# Buck_Boost_Converter.net
KiCad netlist of a schematic drawn in Altium Designer
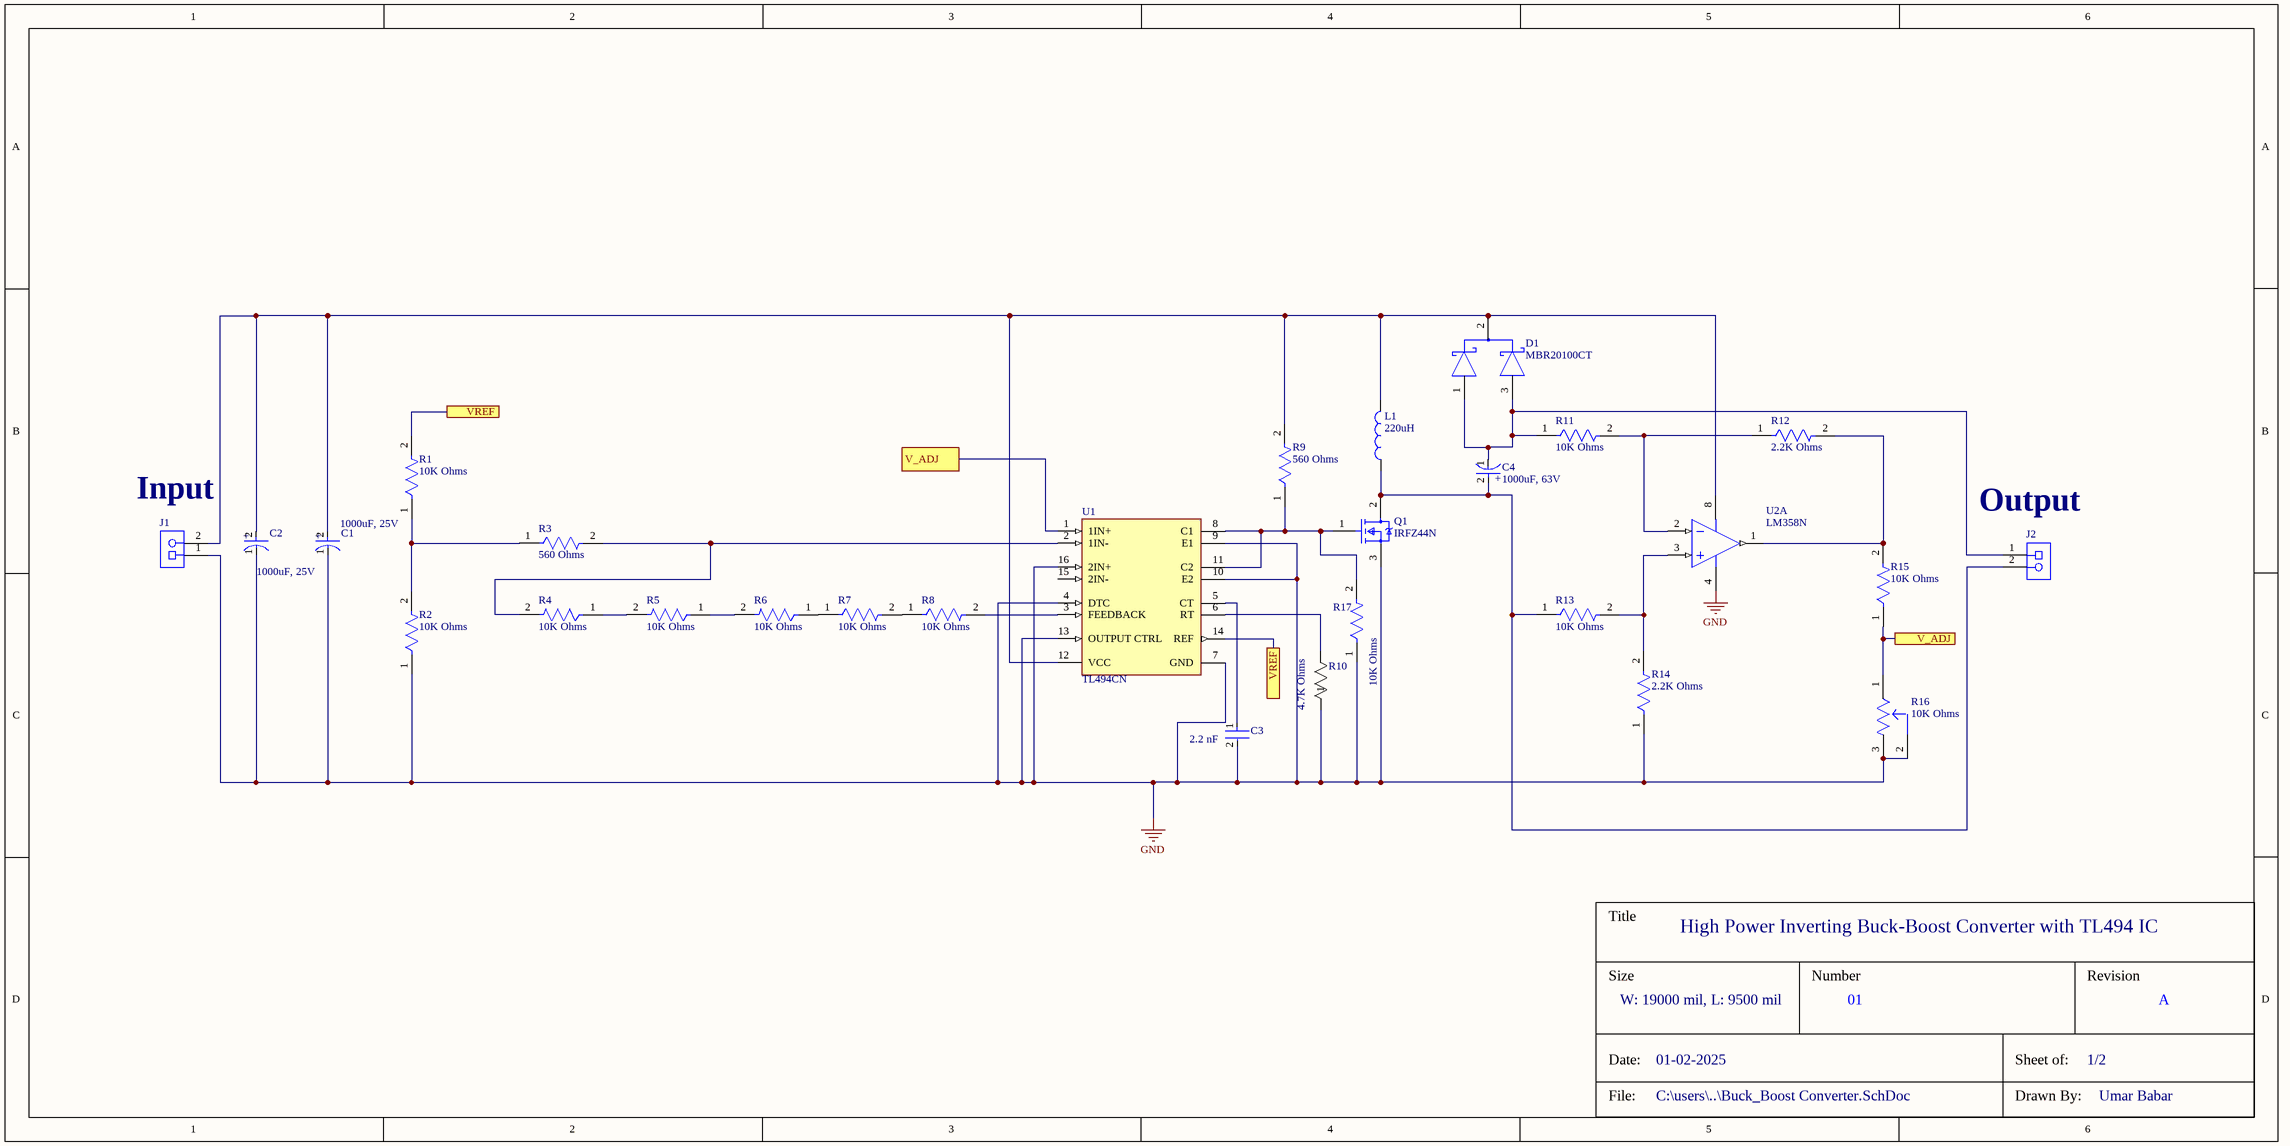
[diagram p0: Buck_Boost Converter.SchDoc]

(export (version "E")
  (design (tool "Eeschema 10.0.6"))
  (components
    (comp (ref "C1")
      (value "1000uF, 25V")
      (footprint "FP-RAD-TH-D_12_5_0_5-L_20-MFG")
      (description "Aluminum Electrolytic Capacitors (Radial Lead Type) 1000uF ±20% 25V")
      (fields (field (name "VOLTAGE") "25V") (field (name "TOLERANCE") "20%"))
      (libsource (lib "Altium Content Vault") (part "a00bbbee19879c290e62620ae7e47b1"))
    )
    (comp (ref "C2")
      (value "1000uF, 25V")
      (footprint "FP-RAD-TH-D_12_5_0_5-L_20-MFG")
      (description "Aluminum Electrolytic Capacitors (Radial Lead Type) 1000uF ±20% 25V")
      (fields (field (name "VOLTAGE") "25V") (field (name "TOLERANCE") "20%"))
      (libsource (lib "Altium Content Vault") (part "a00bbbee19879c290e62620ae7e47b1"))
    )
    (comp (ref "C3")
      (value "2.2 nF")
      (footprint "FP-VY1470-MFG")
      (description "CAP CER 2200PF 760VAC Y5U RADIAL")
      (fields (field (name "VOLTAGE") "500V") (field (name "TOLERANCE") "20%"))
      (libsource (lib "Altium Content Vault") (part "11868f565c42a9108669ba33697ecf6"))
    )
    (comp (ref "C4")
      (value "1000uF, 63V")
      (footprint "FP-RAD-TH-D_16_0_5-L_25_2-MFG")
      (description "Aluminum Electrolytic Capacitors (Radial Lead Type) AEC-Q200 Qualified 1000uF ±20% 63V")
      (fields (field (name "TOLERANCE") "20%"))
      (libsource (lib "Altium Content Vault") (part "203bc49f2ac43e59fd269a8c329ed05"))
    )
    (comp (ref "D1")
      (value "MBR20100CT")
      (footprint "FP-MBR20100CT-E3-4W-MFG")
      (description "MBR20100CT-E3/4W Dual Common-Cathode High-Voltage Schottky Rectifier")
      (libsource (lib "Altium Content Vault") (part "213139fa27cf652ab25f6c90a0a0ee5"))
    )
    (comp (ref "J1")
      (value "1729128")
      (footprint "PHOE-1729128-2_V")
      (description "PCB Terminal Block, 13.5 A, 400 V, 2-Pin THD, RoHS, Bulk")
      (fields (field (name "MANUFACTURER") "Phoenix Contact"))
      (libsource (lib "Altium Content Vault") (part "CN-2P-F-R2"))
    )
    (comp (ref "J2")
      (value "1729128")
      (footprint "PHOE-1729128-2_V")
      (description "PCB Terminal Block, 13.5 A, 400 V, 2-Pin THD, RoHS, Bulk")
      (fields (field (name "MANUFACTURER") "Phoenix Contact"))
      (libsource (lib "") (part "CN-2P-F-R2_1"))
    )
    (comp (ref "L1")
      (value "220uH")
      (footprint "744115")
      (description "744115 200 µH ±20% Ferrite Toroidal Inductor, 2.2A Idc, 180mO Rdc WE-SI")
      (fields (field (name "TOLERANCE") "20%"))
      (libsource (lib "Altium Content Vault") (part "Inductor - 1"))
    )
    (comp (ref "Q1")
      (value "IRFZ44N")
      (footprint "FP-PG-TO262-3-MFG")
      (description "IRFZ44NLPBF Single N-Channel 55 V 17.5 mOhm 63 nC HEXFET® Power Mosfet - TO-262")
      (libsource (lib "Altium Content Vault") (part "b09f7f152735e370c1ea22a33fa83d6"))
    )
    (comp (ref "R1")
      (value "10K Ohms")
      (footprint "FP-MBB0207-MFG")
      (description "RES 10K OHM 0.6W 1% AXIAL")
      (fields (field (name "TOLERANCE") "1%"))
      (libsource (lib "Altium Content Vault") (part "1029c3af85768c4190bb7ad29bc67b5"))
    )
    (comp (ref "R2")
      (value "10K Ohms")
      (footprint "FP-MBB0207-MFG")
      (description "RES 10K OHM 0.6W 1% AXIAL")
      (fields (field (name "TOLERANCE") "1%"))
      (libsource (lib "Altium Content Vault") (part "1029c3af85768c4190bb7ad29bc67b5"))
    )
    (comp (ref "R3")
      (value "560 Ohms")
      (footprint "FP-PAC03-MFG")
      (description "RES 560 OHM 3W 1% AXIAL")
      (fields (field (name "TOLERANCE") "1%"))
      (libsource (lib "Altium Content Vault") (part "1029c3af85768c4190bb7ad29bc67b5"))
    )
    (comp (ref "R4")
      (value "10K Ohms")
      (footprint "FP-MBB0207-MFG")
      (description "RES 10K OHM 0.6W 1% AXIAL")
      (fields (field (name "TOLERANCE") "1%"))
      (libsource (lib "Altium Content Vault") (part "1029c3af85768c4190bb7ad29bc67b5"))
    )
    (comp (ref "R5")
      (value "10K Ohms")
      (footprint "FP-MBB0207-MFG")
      (description "RES 10K OHM 0.6W 1% AXIAL")
      (fields (field (name "TOLERANCE") "1%"))
      (libsource (lib "Altium Content Vault") (part "1029c3af85768c4190bb7ad29bc67b5"))
    )
    (comp (ref "R6")
      (value "10K Ohms")
      (footprint "FP-MBB0207-MFG")
      (description "RES 10K OHM 0.6W 1% AXIAL")
      (fields (field (name "TOLERANCE") "1%"))
      (libsource (lib "Altium Content Vault") (part "1029c3af85768c4190bb7ad29bc67b5"))
    )
    (comp (ref "R7")
      (value "10K Ohms")
      (footprint "FP-MBB0207-MFG")
      (description "RES 10K OHM 0.6W 1% AXIAL")
      (fields (field (name "TOLERANCE") "1%"))
      (libsource (lib "Altium Content Vault") (part "1029c3af85768c4190bb7ad29bc67b5"))
    )
    (comp (ref "R8")
      (value "10K Ohms")
      (footprint "FP-MBB0207-MFG")
      (description "RES 10K OHM 0.6W 1% AXIAL")
      (fields (field (name "TOLERANCE") "1%"))
      (libsource (lib "Altium Content Vault") (part "1029c3af85768c4190bb7ad29bc67b5"))
    )
    (comp (ref "R9")
      (value "560 Ohms")
      (footprint "FP-PAC03-MFG")
      (description "RES 560 OHM 3W 1% AXIAL")
      (fields (field (name "TOLERANCE") "1%"))
      (libsource (lib "Altium Content Vault") (part "1029c3af85768c4190bb7ad29bc67b5"))
    )
    (comp (ref "R10")
      (value "4.7K Ohms")
      (footprint "RES_AC05_VIS")
      (fields (field (name "TOLERANCE") "5%"))
      (libsource (lib "Altium Content Vault") (part "AC05000004701JAC00"))
    )
    (comp (ref "R11")
      (value "10K Ohms")
      (footprint "FP-MBB0207-MFG")
      (description "RES 10K OHM 0.6W 1% AXIAL")
      (fields (field (name "TOLERANCE") "1%"))
      (libsource (lib "Altium Content Vault") (part "1029c3af85768c4190bb7ad29bc67b5"))
    )
    (comp (ref "R12")
      (value "2.2K Ohms")
      (footprint "FP-CFR50J2K2-MFG")
      (description "RES 2.2K OHM 5% 1/2W AXIAL")
      (fields (field (name "TOLERANCE") "5%"))
      (libsource (lib "Altium Content Vault") (part "1029c3af85768c4190bb7ad29bc67b5"))
    )
    (comp (ref "R13")
      (value "10K Ohms")
      (footprint "FP-MBB0207-MFG")
      (description "RES 10K OHM 0.6W 1% AXIAL")
      (fields (field (name "TOLERANCE") "1%"))
      (libsource (lib "Altium Content Vault") (part "1029c3af85768c4190bb7ad29bc67b5"))
    )
    (comp (ref "R14")
      (value "2.2K Ohms")
      (footprint "FP-CFR50J2K2-MFG")
      (description "RES 2.2K OHM 5% 1/2W AXIAL")
      (fields (field (name "TOLERANCE") "5%"))
      (libsource (lib "Altium Content Vault") (part "1029c3af85768c4190bb7ad29bc67b5"))
    )
    (comp (ref "R15")
      (value "10K Ohms")
      (footprint "FP-MBB0207-MFG")
      (description "RES 10K OHM 0.6W 1% AXIAL")
      (fields (field (name "TOLERANCE") "1%"))
      (libsource (lib "Altium Content Vault") (part "1029c3af85768c4190bb7ad29bc67b5"))
    )
    (comp (ref "R16")
      (value "10K Ohms")
      (footprint "FP-3266W-MFG")
      (description "TRIMMER 10K OHM 0.25W PC PIN TOP")
      (fields
        (field (name "MANUFACTURER") "Bourns")
        (field (name "OCTOPART") "https://octopart.com/3266w-1-103lf-bourns-81445")
      )
      (libsource (lib "Altium Content Vault") (part "5aa38b60e553f01fbee9df648f8b81b"))
    )
    (comp (ref "R17")
      (value "10K Ohms")
      (footprint "FP-MBB0207-MFG")
      (description "RES 10K OHM 0.6W 1% AXIAL")
      (fields (field (name "TOLERANCE") "1%"))
      (libsource (lib "Altium Content Vault") (part "1029c3af85768c4190bb7ad29bc67b5"))
    )
    (comp (ref "U1")
      (value "TL494CN")
      (footprint "N0016A")
      (fields (field (name "MANUFACTURER") "Texas Instruments"))
      (libsource (lib "Altium Content Vault") (part "TI-494N16"))
    )
    (comp (ref "U2")
      (value "LM358N")
      (footprint "ONSC-PDIP-8-626-05_M")
      (description "Single Supply Dual Operational Amplifier, 3 to 32 V, 0 to 70 degC, 8-Pin PDIP, Tube")
      (fields (field (name "MANUFACTURER") "On Semiconductor"))
      (libsource (lib "Altium Content Vault") (part "ONSC-LM358_NCV2904-8"))
    )
  )
  (nets
    (net (code "1") (name "/VREF") (class "Default")
      (node (ref "R1") (pin "2") (pinfunction "2_2") (pintype "passive"))
      (node (ref "U1") (pin "14") (pinfunction "REF_14") (pintype "output"))
    )
    (net (code "2") (name "/V_ADJ") (class "Default")
      (node (ref "R15") (pin "1") (pinfunction "1_1") (pintype "passive"))
      (node (ref "R16") (pin "1") (pinfunction "CCW_1") (pintype "passive"))
      (node (ref "U1") (pin "1") (pinfunction "1IN+_1") (pintype "input"))
    )
    (net (code "3") (name "GND") (class "Default")
      (node (ref "C1") (pin "1") (pinfunction "C_1") (pintype "passive"))
      (node (ref "C2") (pin "1") (pinfunction "C_1") (pintype "passive"))
      (node (ref "C3") (pin "2") (pinfunction "2_2") (pintype "passive"))
      (node (ref "J1") (pin "1") (pinfunction "1_1") (pintype "passive"))
      (node (ref "Q1") (pin "3") (pinfunction "S_3") (pintype "passive"))
      (node (ref "R10") (pin "1") (pinfunction "1_1") (pintype "passive"))
      (node (ref "R14") (pin "1") (pinfunction "1_1") (pintype "passive"))
      (node (ref "R16") (pin "2") (pinfunction "WIPER_2") (pintype "passive"))
      (node (ref "R16") (pin "3") (pinfunction "CW_3") (pintype "passive"))
      (node (ref "R17") (pin "1") (pinfunction "1_1") (pintype "passive"))
      (node (ref "R2") (pin "1") (pinfunction "1_1") (pintype "passive"))
      (node (ref "U1") (pin "10") (pinfunction "E2_10") (pintype "passive"))
      (node (ref "U1") (pin "13") (pinfunction "OUTPUT_CTRL_13") (pintype "input"))
      (node (ref "U1") (pin "16") (pinfunction "2IN+_16") (pintype "input"))
      (node (ref "U1") (pin "4") (pinfunction "DTC_4") (pintype "input"))
      (node (ref "U1") (pin "7") (pinfunction "GND_7") (pintype "power_in"))
      (node (ref "U1") (pin "9") (pinfunction "E1_9") (pintype "passive"))
      (node (ref "U2") (pin "4") (pinfunction "VEE/GND_4") (pintype "power_in"))
    )
    (net (code "4") (name "Net-(C1-A)") (class "Default")
      (node (ref "C1") (pin "2") (pinfunction "A_2") (pintype "passive"))
      (node (ref "C2") (pin "2") (pinfunction "A_2") (pintype "passive"))
      (node (ref "D1") (pin "2") (pinfunction "COMMON_CATHODE_2") (pintype "passive"))
      (node (ref "J1") (pin "2") (pinfunction "2_2") (pintype "passive"))
      (node (ref "L1") (pin "2") (pinfunction "2_2") (pintype "passive"))
      (node (ref "R9") (pin "2") (pinfunction "2_2") (pintype "passive"))
      (node (ref "U1") (pin "12") (pinfunction "VCC_12") (pintype "power_in"))
      (node (ref "U2") (pin "8") (pinfunction "VCC_8") (pintype "power_in"))
    )
    (net (code "5") (name "Net-(C4-A)") (class "Default")
      (node (ref "C4") (pin "2") (pinfunction "A_2") (pintype "passive"))
      (node (ref "J2") (pin "2") (pinfunction "2_2") (pintype "passive"))
      (node (ref "L1") (pin "1") (pinfunction "1_1") (pintype "passive"))
      (node (ref "Q1") (pin "2") (pinfunction "D_2") (pintype "passive"))
      (node (ref "R13") (pin "1") (pinfunction "1_1") (pintype "passive"))
    )
    (net (code "6") (name "Net-(C4-C)") (class "Default")
      (node (ref "C4") (pin "1") (pinfunction "C_1") (pintype "passive"))
      (node (ref "D1") (pin "1") (pinfunction "1_ANODE_1") (pintype "passive"))
      (node (ref "D1") (pin "3") (pinfunction "2_ANODE_3") (pintype "passive"))
      (node (ref "J2") (pin "1") (pinfunction "1_1") (pintype "passive"))
      (node (ref "R11") (pin "1") (pinfunction "1_1") (pintype "passive"))
    )
    (net (code "7") (name "Net-(Q1-G)") (class "Default")
      (node (ref "Q1") (pin "1") (pinfunction "G_1") (pintype "passive"))
      (node (ref "R17") (pin "2") (pinfunction "2_2") (pintype "passive"))
      (node (ref "R9") (pin "1") (pinfunction "1_1") (pintype "passive"))
      (node (ref "U1") (pin "11") (pinfunction "C2_11") (pintype "passive"))
      (node (ref "U1") (pin "8") (pinfunction "C1_8") (pintype "passive"))
    )
    (net (code "8") (name "Net-(R1-Pad1)") (class "Default")
      (node (ref "R1") (pin "1") (pinfunction "1_1") (pintype "passive"))
      (node (ref "R2") (pin "2") (pinfunction "2_2") (pintype "passive"))
      (node (ref "R3") (pin "1") (pinfunction "1_1") (pintype "passive"))
    )
    (net (code "9") (name "Net-(R4-Pad1)") (class "Default")
      (node (ref "R4") (pin "1") (pinfunction "1_1") (pintype "passive"))
      (node (ref "R5") (pin "2") (pinfunction "2_2") (pintype "passive"))
    )
    (net (code "10") (name "Net-(R5-Pad1)") (class "Default")
      (node (ref "R5") (pin "1") (pinfunction "1_1") (pintype "passive"))
      (node (ref "R6") (pin "2") (pinfunction "2_2") (pintype "passive"))
    )
    (net (code "11") (name "Net-(R6-Pad1)") (class "Default")
      (node (ref "R6") (pin "1") (pinfunction "1_1") (pintype "passive"))
      (node (ref "R7") (pin "1") (pinfunction "1_1") (pintype "passive"))
    )
    (net (code "12") (name "Net-(R7-Pad2)") (class "Default")
      (node (ref "R7") (pin "2") (pinfunction "2_2") (pintype "passive"))
      (node (ref "R8") (pin "1") (pinfunction "1_1") (pintype "passive"))
    )
    (net (code "13") (name "Net-(U1-1IN-)") (class "Default")
      (node (ref "R3") (pin "2") (pinfunction "2_2") (pintype "passive"))
      (node (ref "R4") (pin "2") (pinfunction "2_2") (pintype "passive"))
      (node (ref "U1") (pin "2") (pinfunction "1IN-_2") (pintype "input"))
    )
    (net (code "14") (name "Net-(U1-CT)") (class "Default")
      (node (ref "C3") (pin "1") (pinfunction "1_1") (pintype "passive"))
      (node (ref "U1") (pin "5") (pinfunction "CT_5") (pintype "passive"))
    )
    (net (code "15") (name "Net-(U1-FEEDBACK)") (class "Default")
      (node (ref "R8") (pin "2") (pinfunction "2_2") (pintype "passive"))
      (node (ref "U1") (pin "3") (pinfunction "FEEDBACK_3") (pintype "input"))
    )
    (net (code "16") (name "Net-(U1-RT)") (class "Default")
      (node (ref "R10") (pin "2") (pinfunction "2_2") (pintype "passive"))
      (node (ref "U1") (pin "6") (pinfunction "RT_6") (pintype "passive"))
    )
    (net (code "17") (name "Net-(U2A-INA+)") (class "Default")
      (node (ref "R13") (pin "2") (pinfunction "2_2") (pintype "passive"))
      (node (ref "R14") (pin "2") (pinfunction "2_2") (pintype "passive"))
      (node (ref "U2") (pin "3") (pinfunction "INA+_3") (pintype "input"))
    )
    (net (code "18") (name "Net-(U2A-INA-)") (class "Default")
      (node (ref "R11") (pin "2") (pinfunction "2_2") (pintype "passive"))
      (node (ref "R12") (pin "1") (pinfunction "1_1") (pintype "passive"))
      (node (ref "U2") (pin "2") (pinfunction "INA-_2") (pintype "input"))
    )
    (net (code "19") (name "Net-(U2A-OUTA)") (class "Default")
      (node (ref "R12") (pin "2") (pinfunction "2_2") (pintype "passive"))
      (node (ref "R15") (pin "2") (pinfunction "2_2") (pintype "passive"))
      (node (ref "U2") (pin "1") (pinfunction "OUTA_1") (pintype "output"))
    )
    (net (code "20") (name "unconnected-(U1-2IN--Pad15)") (class "Default")
      (node (ref "U1") (pin "15") (pinfunction "2IN-_15") (pintype "input"))
    )
  )
)
